# ESP32_Weather.net
KiCad netlist of a schematic drawn in EAGLE
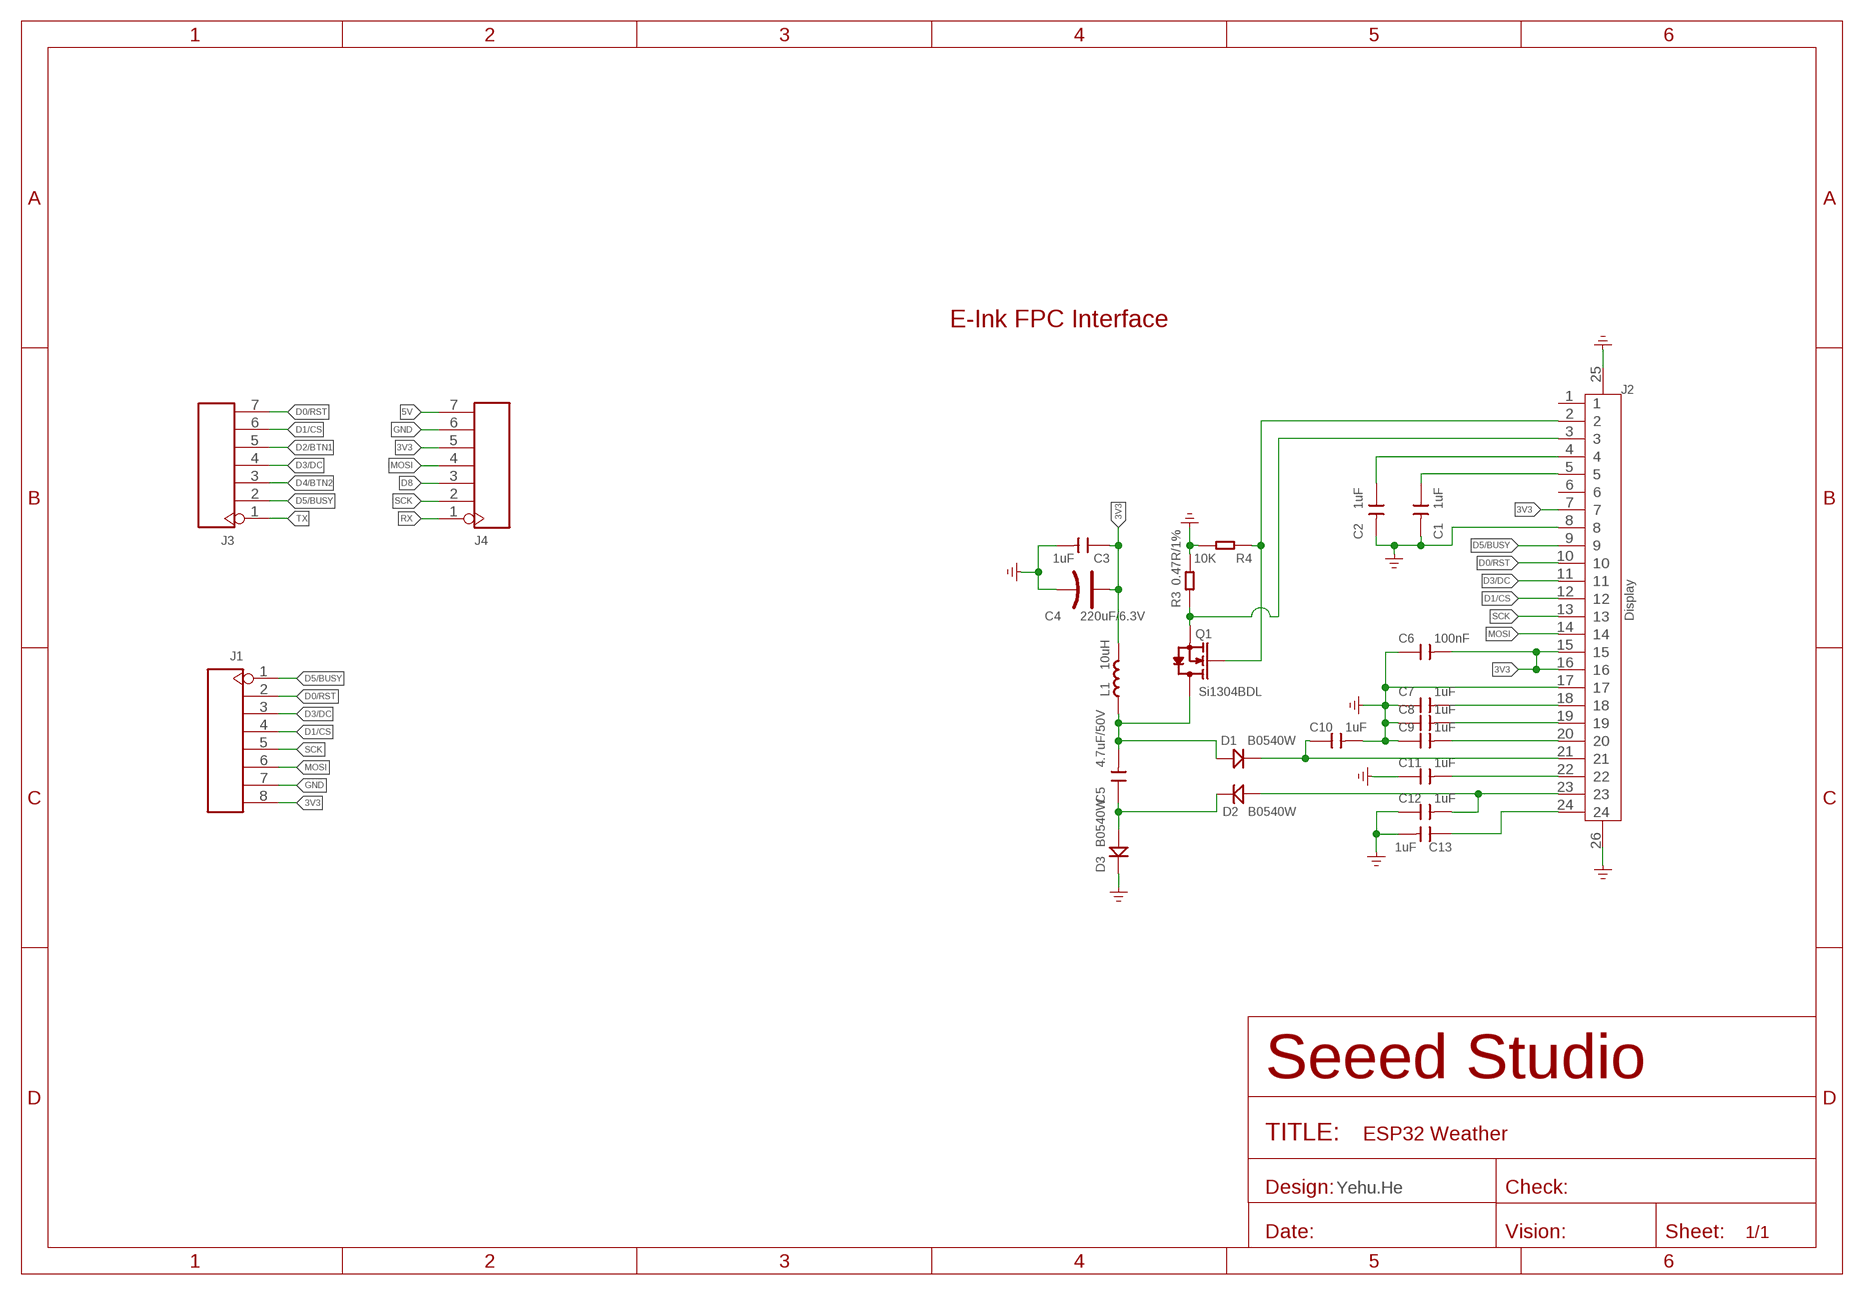
[diagram p0: schematic, sheet 1]

(export (version "E")
  (design (tool "Eeschema 10.0.6"))
  (components
    (comp (ref "C1")
      (value "1uF")
      (footprint "eagle-import:C0603")
      (libsource (lib "eagle-import") (part "CAP-0603"))
    )
    (comp (ref "C2")
      (value "1uF")
      (footprint "eagle-import:C0603")
      (libsource (lib "eagle-import") (part "CAP-0603"))
    )
    (comp (ref "C3")
      (value "1uF")
      (footprint "eagle-import:C0603")
      (libsource (lib "eagle-import") (part "CAP-0603"))
    )
    (comp (ref "C4")
      (value "220uF/6.3V")
      (footprint "eagle-import:AVX-B")
      (libsource (lib "eagle-import") (part "CAP-POLAR-AVX-B"))
    )
    (comp (ref "C5")
      (value "4.7uF/50V")
      (footprint "eagle-import:C1206")
      (libsource (lib "eagle-import") (part "CAP-1206"))
    )
    (comp (ref "C6")
      (value "100nF")
      (footprint "eagle-import:C0603")
      (libsource (lib "eagle-import") (part "CAP-0603"))
    )
    (comp (ref "C7")
      (value "1uF")
      (footprint "eagle-import:C0603")
      (libsource (lib "eagle-import") (part "CAP-0603"))
    )
    (comp (ref "C8")
      (value "1uF")
      (footprint "eagle-import:C0603")
      (libsource (lib "eagle-import") (part "CAP-0603"))
    )
    (comp (ref "C9")
      (value "1uF")
      (footprint "eagle-import:C0603")
      (libsource (lib "eagle-import") (part "CAP-0603"))
    )
    (comp (ref "C10")
      (value "1uF")
      (footprint "eagle-import:C0603")
      (libsource (lib "eagle-import") (part "CAP-0603"))
    )
    (comp (ref "C11")
      (value "1uF")
      (footprint "eagle-import:C0603")
      (libsource (lib "eagle-import") (part "CAP-0603"))
    )
    (comp (ref "C12")
      (value "1uF")
      (footprint "eagle-import:C0603")
      (libsource (lib "eagle-import") (part "CAP-0603"))
    )
    (comp (ref "C13")
      (value "1uF")
      (footprint "eagle-import:C0603")
      (libsource (lib "eagle-import") (part "CAP-0603"))
    )
    (comp (ref "D1")
      (value "B0540W")
      (footprint "eagle-import:SOD-323")
      (libsource (lib "eagle-import") (part "DIODE'0805'"))
    )
    (comp (ref "D2")
      (value "B0540W")
      (footprint "eagle-import:SOD-323")
      (libsource (lib "eagle-import") (part "DIODE'0805'"))
    )
    (comp (ref "D3")
      (value "B0540W")
      (footprint "eagle-import:SOD-323")
      (libsource (lib "eagle-import") (part "DIODE'0805'"))
    )
    (comp (ref "J1")
      (value "HEADER-8P-80/40MIL")
      (footprint "eagle-import:H8-2.54-C80D40MIL")
      (libsource (lib "eagle-import") (part "HEADER-8P-80/40MIL"))
    )
    (comp (ref "J2")
      (value "Display")
      (footprint "eagle-import:FPCB24-SMD-0.5-17.6X5.0X2MM")
      (libsource (lib "eagle-import") (part "FPC-CONNECTOR-24P"))
    )
    (comp (ref "J3")
      (value "HEADER-7P-18.28X2.5")
      (footprint "eagle-import:H7-2.54-18.28X2.5X5MM")
      (libsource (lib "eagle-import") (part "HEADER-7P-18.28X2.5"))
    )
    (comp (ref "J4")
      (value "HEADER-7P-18.28X2.5")
      (footprint "eagle-import:H7-2.54-18.28X2.5X5MM")
      (libsource (lib "eagle-import") (part "HEADER-7P-18.28X2.5"))
    )
    (comp (ref "L1")
      (value "10uH")
      (footprint "eagle-import:L0420")
      (libsource (lib "eagle-import") (part "INDUCTOR-SPD3D16-4R7M"))
    )
    (comp (ref "Q1")
      (value "Si1304BDL")
      (footprint "eagle-import:SOT-323")
      (libsource (lib "eagle-import") (part "MOSFET-N'SI1304BDL'"))
    )
    (comp (ref "R3")
      (value "0.47R/1%")
      (footprint "eagle-import:R0603")
      (libsource (lib "eagle-import") (part "RES-0603"))
    )
    (comp (ref "R4")
      (value "10K")
      (footprint "eagle-import:R0603")
      (libsource (lib "eagle-import") (part "RES-0603"))
    )
  )
  (nets
    (net (code "1") (name "3V3") (class "Default")
      (node (ref "C3") (pin "1") (pinfunction "1_1") (pintype "passive"))
      (node (ref "C4") (pin "+") (pinfunction "+_+") (pintype "passive"))
      (node (ref "C6") (pin "2") (pinfunction "2_2") (pintype "passive"))
      (node (ref "J1") (pin "8") (pinfunction "8_8") (pintype "bidirectional"))
      (node (ref "J2") (pin "15") (pinfunction "15_15") (pintype "bidirectional"))
      (node (ref "J2") (pin "16") (pinfunction "16_16") (pintype "bidirectional"))
      (node (ref "J2") (pin "7") (pinfunction "7_7") (pintype "bidirectional"))
      (node (ref "J4") (pin "5") (pinfunction "5_5") (pintype "bidirectional"))
      (node (ref "L1") (pin "2") (pinfunction "2_2") (pintype "passive"))
    )
    (net (code "2") (name "5V") (class "Default")
      (node (ref "J4") (pin "7") (pinfunction "7_7") (pintype "bidirectional"))
    )
    (net (code "3") (name "D0{slash}RST") (class "Default")
      (node (ref "J1") (pin "2") (pinfunction "2_2") (pintype "bidirectional"))
      (node (ref "J2") (pin "10") (pinfunction "10_10") (pintype "bidirectional"))
      (node (ref "J3") (pin "7") (pinfunction "7_7") (pintype "bidirectional"))
    )
    (net (code "4") (name "D1{slash}CS") (class "Default")
      (node (ref "J1") (pin "4") (pinfunction "4_4") (pintype "bidirectional"))
      (node (ref "J2") (pin "12") (pinfunction "12_12") (pintype "bidirectional"))
      (node (ref "J3") (pin "6") (pinfunction "6_6") (pintype "bidirectional"))
    )
    (net (code "5") (name "D2{slash}BTN1") (class "Default")
      (node (ref "J3") (pin "5") (pinfunction "5_5") (pintype "bidirectional"))
    )
    (net (code "6") (name "D3{slash}DC") (class "Default")
      (node (ref "J1") (pin "3") (pinfunction "3_3") (pintype "bidirectional"))
      (node (ref "J2") (pin "11") (pinfunction "11_11") (pintype "bidirectional"))
      (node (ref "J3") (pin "4") (pinfunction "4_4") (pintype "bidirectional"))
    )
    (net (code "7") (name "D4{slash}BTN2") (class "Default")
      (node (ref "J3") (pin "3") (pinfunction "3_3") (pintype "bidirectional"))
    )
    (net (code "8") (name "D5{slash}BUSY") (class "Default")
      (node (ref "J1") (pin "1") (pinfunction "1_1") (pintype "bidirectional"))
      (node (ref "J2") (pin "9") (pinfunction "9_9") (pintype "bidirectional"))
      (node (ref "J3") (pin "2") (pinfunction "2_2") (pintype "bidirectional"))
    )
    (net (code "9") (name "D8") (class "Default")
      (node (ref "J4") (pin "3") (pinfunction "3_3") (pintype "bidirectional"))
    )
    (net (code "10") (name "GND") (class "Default")
      (node (ref "C1") (pin "2") (pinfunction "2_2") (pintype "passive"))
      (node (ref "C10") (pin "2") (pinfunction "2_2") (pintype "passive"))
      (node (ref "C11") (pin "1") (pinfunction "1_1") (pintype "passive"))
      (node (ref "C12") (pin "1") (pinfunction "1_1") (pintype "passive"))
      (node (ref "C13") (pin "2") (pinfunction "2_2") (pintype "passive"))
      (node (ref "C2") (pin "2") (pinfunction "2_2") (pintype "passive"))
      (node (ref "C3") (pin "2") (pinfunction "2_2") (pintype "passive"))
      (node (ref "C4") (pin "-") (pinfunction "-_-") (pintype "passive"))
      (node (ref "C6") (pin "1") (pinfunction "1_1") (pintype "passive"))
      (node (ref "C7") (pin "1") (pinfunction "1_1") (pintype "passive"))
      (node (ref "C8") (pin "1") (pinfunction "1_1") (pintype "passive"))
      (node (ref "C9") (pin "1") (pinfunction "1_1") (pintype "passive"))
      (node (ref "D3") (pin "-") (pinfunction "-_-") (pintype "passive"))
      (node (ref "J1") (pin "7") (pinfunction "7_7") (pintype "bidirectional"))
      (node (ref "J2") (pin "17") (pinfunction "17_17") (pintype "bidirectional"))
      (node (ref "J2") (pin "25") (pinfunction "P1_25") (pintype "bidirectional"))
      (node (ref "J2") (pin "26") (pinfunction "P2_26") (pintype "bidirectional"))
      (node (ref "J2") (pin "8") (pinfunction "8_8") (pintype "bidirectional"))
      (node (ref "J4") (pin "6") (pinfunction "6_6") (pintype "bidirectional"))
      (node (ref "R3") (pin "2") (pinfunction "2_2") (pintype "passive"))
      (node (ref "R4") (pin "2") (pinfunction "2_2") (pintype "passive"))
    )
    (net (code "11") (name "MOSI") (class "Default")
      (node (ref "J1") (pin "6") (pinfunction "6_6") (pintype "bidirectional"))
      (node (ref "J2") (pin "14") (pinfunction "14_14") (pintype "bidirectional"))
      (node (ref "J4") (pin "4") (pinfunction "4_4") (pintype "bidirectional"))
    )
    (net (code "12") (name "Net-(C1-Pad1)") (class "Default")
      (node (ref "C1") (pin "1") (pinfunction "1_1") (pintype "passive"))
      (node (ref "J2") (pin "5") (pinfunction "5_5") (pintype "bidirectional"))
    )
    (net (code "13") (name "Net-(C2-Pad1)") (class "Default")
      (node (ref "C2") (pin "1") (pinfunction "1_1") (pintype "passive"))
      (node (ref "J2") (pin "4") (pinfunction "4_4") (pintype "bidirectional"))
    )
    (net (code "14") (name "Net-(C5-Pad1)") (class "Default")
      (node (ref "C5") (pin "1") (pinfunction "1_1") (pintype "passive"))
      (node (ref "D2") (pin "-") (pinfunction "-_-") (pintype "passive"))
      (node (ref "D3") (pin "+") (pinfunction "+_+") (pintype "passive"))
    )
    (net (code "15") (name "Net-(C7-Pad2)") (class "Default")
      (node (ref "C7") (pin "2") (pinfunction "2_2") (pintype "passive"))
      (node (ref "J2") (pin "18") (pinfunction "18_18") (pintype "bidirectional"))
    )
    (net (code "16") (name "Net-(C8-Pad2)") (class "Default")
      (node (ref "C8") (pin "2") (pinfunction "2_2") (pintype "passive"))
      (node (ref "J2") (pin "19") (pinfunction "19_19") (pintype "bidirectional"))
    )
    (net (code "17") (name "Net-(C9-Pad2)") (class "Default")
      (node (ref "C9") (pin "2") (pinfunction "2_2") (pintype "passive"))
      (node (ref "J2") (pin "20") (pinfunction "20_20") (pintype "bidirectional"))
    )
    (net (code "18") (name "Net-(C10-Pad1)") (class "Default")
      (node (ref "C10") (pin "1") (pinfunction "1_1") (pintype "passive"))
      (node (ref "D1") (pin "-") (pinfunction "-_-") (pintype "passive"))
      (node (ref "J2") (pin "21") (pinfunction "21_21") (pintype "bidirectional"))
    )
    (net (code "19") (name "Net-(C11-Pad2)") (class "Default")
      (node (ref "C11") (pin "2") (pinfunction "2_2") (pintype "passive"))
      (node (ref "J2") (pin "22") (pinfunction "22_22") (pintype "bidirectional"))
    )
    (net (code "20") (name "Net-(C12-Pad2)") (class "Default")
      (node (ref "C12") (pin "2") (pinfunction "2_2") (pintype "passive"))
      (node (ref "D2") (pin "+") (pinfunction "+_+") (pintype "passive"))
      (node (ref "J2") (pin "23") (pinfunction "23_23") (pintype "bidirectional"))
    )
    (net (code "21") (name "Net-(C13-Pad1)") (class "Default")
      (node (ref "C13") (pin "1") (pinfunction "1_1") (pintype "passive"))
      (node (ref "J2") (pin "24") (pinfunction "24_24") (pintype "bidirectional"))
    )
    (net (code "22") (name "Net-(Q1-D)") (class "Default")
      (node (ref "C5") (pin "2") (pinfunction "2_2") (pintype "passive"))
      (node (ref "D1") (pin "+") (pinfunction "+_+") (pintype "passive"))
      (node (ref "L1") (pin "1") (pinfunction "1_1") (pintype "passive"))
      (node (ref "Q1") (pin "3") (pinfunction "D_3") (pintype "passive"))
    )
    (net (code "23") (name "Net-(Q1-G)") (class "Default")
      (node (ref "J2") (pin "2") (pinfunction "2_2") (pintype "bidirectional"))
      (node (ref "Q1") (pin "1") (pinfunction "G_1") (pintype "passive"))
      (node (ref "R4") (pin "1") (pinfunction "1_1") (pintype "passive"))
    )
    (net (code "24") (name "Net-(Q1-S)") (class "Default")
      (node (ref "J2") (pin "3") (pinfunction "3_3") (pintype "bidirectional"))
      (node (ref "Q1") (pin "2") (pinfunction "S_2") (pintype "passive"))
      (node (ref "R3") (pin "1") (pinfunction "1_1") (pintype "passive"))
    )
    (net (code "25") (name "RX") (class "Default")
      (node (ref "J4") (pin "1") (pinfunction "1_1") (pintype "bidirectional"))
    )
    (net (code "26") (name "SCK") (class "Default")
      (node (ref "J1") (pin "5") (pinfunction "5_5") (pintype "bidirectional"))
      (node (ref "J2") (pin "13") (pinfunction "13_13") (pintype "bidirectional"))
      (node (ref "J4") (pin "2") (pinfunction "2_2") (pintype "bidirectional"))
    )
    (net (code "27") (name "TX") (class "Default")
      (node (ref "J3") (pin "1") (pinfunction "1_1") (pintype "bidirectional"))
    )
    (net (code "28") (name "unconnected-(J2-Pad1)") (class "Default")
      (node (ref "J2") (pin "1") (pinfunction "1_1") (pintype "bidirectional"))
    )
    (net (code "29") (name "unconnected-(J2-Pad6)") (class "Default")
      (node (ref "J2") (pin "6") (pinfunction "6_6") (pintype "bidirectional"))
    )
  )
)
